# Sheet1.net
KiCad netlist of a schematic drawn in Altium Designer
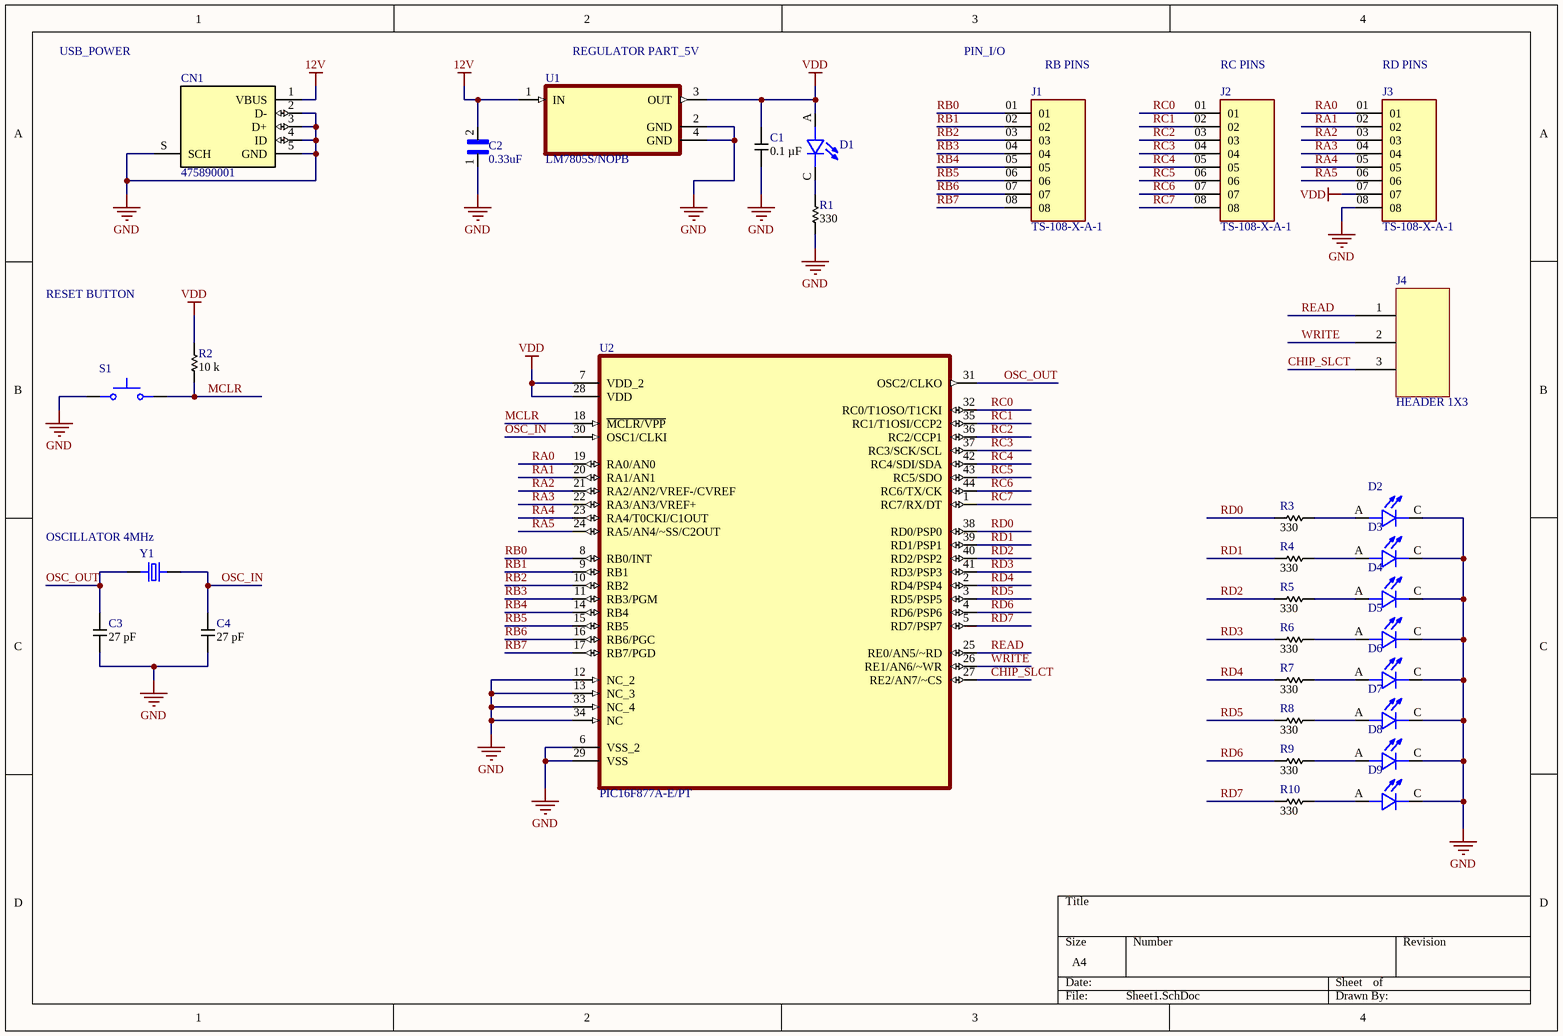
[diagram p0: Sheet1.SchDoc]

(export (version "E")
  (design (tool "Eeschema 10.0.6"))
  (components
    (comp (ref "C1")
      (value "CL10B104KB8NNNC")
      (footprint "SAMSUNG_CAP_0603_090")
      (description "CAP CER 0.1UF 50V X7R 0603")
      (fields (field (name "CAPACITANCE") "0.1 µF"))
      (libsource (lib "Ceramic Capacitors") (part "CL10B104KB8NNNC"))
    )
    (comp (ref "C2")
      (value "0.33uF")
      (footprint "CAPC1608X90N")
      (description "0.33 ÂµF Â±10% 50V Ceramic Capacitor X7R 0603 (1608 Metric)")
      (fields (field (name "MP") "C1608X7R1H334K080AC") (field (name "MF") "TDK"))
      (libsource (lib "C1608X7R1H334K080AC_0.33uF") (part "C1608X7R1H334K080AC"))
    )
    (comp (ref "C3")
      (value "CL21C270JBANNNC")
      (footprint "SAMSUNG_CAP_0805_075")
      (description "CAP CER 27PF 50V C0G/NP0 0805")
      (fields (field (name "CAPACITANCE") "27 pF"))
      (libsource (lib "Ceramic Capacitors") (part "CL21C270JBANNNC"))
    )
    (comp (ref "C4")
      (value "CL21C270JBANNNC")
      (footprint "SAMSUNG_CAP_0805_075")
      (description "CAP CER 27PF 50V C0G/NP0 0805")
      (fields (field (name "CAPACITANCE") "27 pF"))
      (libsource (lib "Ceramic Capacitors") (part "CL21C270JBANNNC"))
    )
    (comp (ref "CN1")
      (value "475890001")
      (footprint "MOLEX_475890001")
      (description "CONN RCPT MICRO USB AB 5P SMD RA")
      (libsource (lib "USB, DVI, HDMI Connectors") (part "475890001"))
    )
    (comp (ref "D1")
      (value "MP-2016-1100-30-80")
      (footprint "LED_MP-2016-1100-30-80")
      (description "LED Midpower Lighting series White, warm 3000K, 80 CRI, 27lm 3V 120mA 110Â°")
      (fields (field (name "MF") "Luminus Devices"))
      (libsource (lib "") (part "MP-2016-1100-30-80_1"))
    )
    (comp (ref "D2")
      (value "MP-2016-1100-30-80")
      (footprint "LED_MP-2016-1100-30-80")
      (description "LED Midpower Lighting series White, warm 3000K, 80 CRI, 27lm 3V 120mA 110Â°")
      (fields (field (name "MF") "Luminus Devices"))
      (libsource (lib "MP-2016-1100-30-80") (part "MP-2016-1100-30-80"))
    )
    (comp (ref "D3")
      (value "MP-2016-1100-30-80")
      (footprint "LED_MP-2016-1100-30-80")
      (description "LED Midpower Lighting series White, warm 3000K, 80 CRI, 27lm 3V 120mA 110Â°")
      (fields (field (name "MF") "Luminus Devices"))
      (libsource (lib "MP-2016-1100-30-80") (part "MP-2016-1100-30-80"))
    )
    (comp (ref "D4")
      (value "MP-2016-1100-30-80")
      (footprint "LED_MP-2016-1100-30-80")
      (description "LED Midpower Lighting series White, warm 3000K, 80 CRI, 27lm 3V 120mA 110Â°")
      (fields (field (name "MF") "Luminus Devices"))
      (libsource (lib "MP-2016-1100-30-80") (part "MP-2016-1100-30-80"))
    )
    (comp (ref "D5")
      (value "MP-2016-1100-30-80")
      (footprint "LED_MP-2016-1100-30-80")
      (description "LED Midpower Lighting series White, warm 3000K, 80 CRI, 27lm 3V 120mA 110Â°")
      (fields (field (name "MF") "Luminus Devices"))
      (libsource (lib "MP-2016-1100-30-80") (part "MP-2016-1100-30-80"))
    )
    (comp (ref "D6")
      (value "MP-2016-1100-30-80")
      (footprint "LED_MP-2016-1100-30-80")
      (description "LED Midpower Lighting series White, warm 3000K, 80 CRI, 27lm 3V 120mA 110Â°")
      (fields (field (name "MF") "Luminus Devices"))
      (libsource (lib "MP-2016-1100-30-80") (part "MP-2016-1100-30-80"))
    )
    (comp (ref "D7")
      (value "MP-2016-1100-30-80")
      (footprint "LED_MP-2016-1100-30-80")
      (description "LED Midpower Lighting series White, warm 3000K, 80 CRI, 27lm 3V 120mA 110Â°")
      (fields (field (name "MF") "Luminus Devices"))
      (libsource (lib "MP-2016-1100-30-80") (part "MP-2016-1100-30-80"))
    )
    (comp (ref "D8")
      (value "MP-2016-1100-30-80")
      (footprint "LED_MP-2016-1100-30-80")
      (description "LED Midpower Lighting series White, warm 3000K, 80 CRI, 27lm 3V 120mA 110Â°")
      (fields (field (name "MF") "Luminus Devices"))
      (libsource (lib "MP-2016-1100-30-80") (part "MP-2016-1100-30-80"))
    )
    (comp (ref "D9")
      (value "MP-2016-1100-30-80")
      (footprint "LED_MP-2016-1100-30-80")
      (description "LED Midpower Lighting series White, warm 3000K, 80 CRI, 27lm 3V 120mA 110Â°")
      (fields (field (name "MF") "Luminus Devices"))
      (libsource (lib "MP-2016-1100-30-80") (part "MP-2016-1100-30-80"))
    )
    (comp (ref "J1")
      (value "TS-108-X-A-1")
      (footprint "SAMTEC_TS-108-X-A-1")
      (description "TS Series .100 Single Row Screw Machine Terminal Strip")
      (fields (field (name "MP") "TS-108-G-A-1") (field (name "MF") "Samtec"))
      (libsource (lib "TS-108-X-A-1") (part "TS-108-X-A-1"))
    )
    (comp (ref "J2")
      (value "TS-108-X-A-1")
      (footprint "SAMTEC_TS-108-X-A-1")
      (description "TS Series .100 Single Row Screw Machine Terminal Strip")
      (fields (field (name "MP") "TS-108-G-A-1") (field (name "MF") "Samtec"))
      (libsource (lib "TS-108-X-A-1") (part "TS-108-X-A-1"))
    )
    (comp (ref "J3")
      (value "TS-108-X-A-1")
      (footprint "SAMTEC_TS-108-X-A-1")
      (description "TS Series .100 Single Row Screw Machine Terminal Strip")
      (fields (field (name "MP") "TS-108-G-A-1") (field (name "MF") "Samtec"))
      (libsource (lib "TS-108-X-A-1") (part "TS-108-X-A-1"))
    )
    (comp (ref "J4")
      (value "HEADER 1X3")
      (footprint "HEADER 1X3_2.54")
      (libsource (lib "Sch1-schlib") (part "HEADER 1X3"))
    )
    (comp (ref "R1")
      (value "0603SAJ0331T5E")
      (footprint "ROYALOHM_RES_0603")
      (description "RES SMD 330R OHM 5% 1/10W 0603")
      (fields (field (name "RESISTANCE") "330"))
      (libsource (lib "Chip Resistor - Surface Mount") (part "0603SAJ0331T5E"))
    )
    (comp (ref "R2")
      (value "0603SAJ0103T5E")
      (footprint "ROYALOHM_RES_0603")
      (description "RES SMD 10K OHM 5% 1/10W 0603")
      (fields (field (name "RESISTANCE") "10 k"))
      (libsource (lib "Chip Resistor - Surface Mount") (part "0603SAJ0103T5E"))
    )
    (comp (ref "R3")
      (value "0603SAJ0331T5E")
      (footprint "ROYALOHM_RES_0603")
      (description "RES SMD 330R OHM 5% 1/10W 0603")
      (fields (field (name "RESISTANCE") "330"))
      (libsource (lib "Chip Resistor - Surface Mount") (part "0603SAJ0331T5E"))
    )
    (comp (ref "R4")
      (value "0603SAJ0331T5E")
      (footprint "ROYALOHM_RES_0603")
      (description "RES SMD 330R OHM 5% 1/10W 0603")
      (fields (field (name "RESISTANCE") "330"))
      (libsource (lib "Chip Resistor - Surface Mount") (part "0603SAJ0331T5E"))
    )
    (comp (ref "R5")
      (value "0603SAJ0331T5E")
      (footprint "ROYALOHM_RES_0603")
      (description "RES SMD 330R OHM 5% 1/10W 0603")
      (fields (field (name "RESISTANCE") "330"))
      (libsource (lib "Chip Resistor - Surface Mount") (part "0603SAJ0331T5E"))
    )
    (comp (ref "R6")
      (value "0603SAJ0331T5E")
      (footprint "ROYALOHM_RES_0603")
      (description "RES SMD 330R OHM 5% 1/10W 0603")
      (fields (field (name "RESISTANCE") "330"))
      (libsource (lib "Chip Resistor - Surface Mount") (part "0603SAJ0331T5E"))
    )
    (comp (ref "R7")
      (value "0603SAJ0331T5E")
      (footprint "ROYALOHM_RES_0603")
      (description "RES SMD 330R OHM 5% 1/10W 0603")
      (fields (field (name "RESISTANCE") "330"))
      (libsource (lib "Chip Resistor - Surface Mount") (part "0603SAJ0331T5E"))
    )
    (comp (ref "R8")
      (value "0603SAJ0331T5E")
      (footprint "ROYALOHM_RES_0603")
      (description "RES SMD 330R OHM 5% 1/10W 0603")
      (fields (field (name "RESISTANCE") "330"))
      (libsource (lib "Chip Resistor - Surface Mount") (part "0603SAJ0331T5E"))
    )
    (comp (ref "R9")
      (value "0603SAJ0331T5E")
      (footprint "ROYALOHM_RES_0603")
      (description "RES SMD 330R OHM 5% 1/10W 0603")
      (fields (field (name "RESISTANCE") "330"))
      (libsource (lib "Chip Resistor - Surface Mount") (part "0603SAJ0331T5E"))
    )
    (comp (ref "R10")
      (value "0603SAJ0331T5E")
      (footprint "ROYALOHM_RES_0603")
      (description "RES SMD 330R OHM 5% 1/10W 0603")
      (fields (field (name "RESISTANCE") "330"))
      (libsource (lib "Chip Resistor - Surface Mount") (part "0603SAJ0331T5E"))
    )
    (comp (ref "S1")
      (value "800AWSP9M2QE")
      (footprint "SW_800AWSP9M2QE")
      (description "Pushbutton Switch SPST-NO Standard Through Hole")
      (fields (field (name "MF") "E-Switch"))
      (libsource (lib "800AWSP9M2QE") (part "800AWSP9M2QE"))
    )
    (comp (ref "U1")
      (value "LM7805S/NOPB")
      (footprint "TO254P1524X483-4N")
      (description "1.5-A, 30-V, linear voltage regulator")
      (fields (field (name "MF") "Texas Instruments"))
      (libsource (lib "LM7805S_NOPB") (part "LM7805S/NOPB"))
    )
    (comp (ref "U2")
      (value "PIC16F877A-E/PT")
      (footprint "QFP80P1200X1200X120-44N")
      (description "PIC PICÂ® 16F Microcontroller IC 8-Bit 20MHz 14KB _8K x 14_ FLASH 44-TQFP _10x10_")
      (fields (field (name "MF") "Microchip"))
      (libsource (lib "SnapEDAsch") (part "PIC16F877A-E/PT"))
    )
    (comp (ref "Y1")
      (value "ECS-40-S-5PX-TR")
      (footprint "XTAL_ECS-40-S-5PX-TR")
      (description "4MHz Â±30ppm Crystal Series 150 Ohms HC-49/US")
      (fields (field (name "MF") "ECS Inc."))
      (libsource (lib "SnapEDAsch") (part "ECS-40-S-5PX-TR"))
    )
  )
  (nets
    (net (code "1") (name "/CHIP_SLCT") (class "Default")
      (node (ref "J4") (pin "3") (pintype "passive"))
      (node (ref "U2") (pin "27") (pinfunction "RE2/AN7/~CS_27") (pintype "bidirectional"))
    )
    (net (code "2") (name "/MCLR") (class "Default")
      (node (ref "R2") (pin "1") (pinfunction "1_1") (pintype "passive"))
      (node (ref "S1") (pin "3") (pinfunction "3_3") (pintype "passive"))
      (node (ref "U2") (pin "18") (pinfunction "~{MCLR/VPP}_18") (pintype "input"))
    )
    (net (code "3") (name "/OSC_IN") (class "Default")
      (node (ref "C4") (pin "2") (pinfunction "2_2") (pintype "passive"))
      (node (ref "U2") (pin "30") (pinfunction "OSC1/CLKI_30") (pintype "input"))
      (node (ref "Y1") (pin "2") (pinfunction "2_2") (pintype "passive"))
    )
    (net (code "4") (name "/OSC_OUT") (class "Default")
      (node (ref "C3") (pin "2") (pinfunction "2_2") (pintype "passive"))
      (node (ref "U2") (pin "31") (pinfunction "OSC2/CLKO_31") (pintype "output"))
      (node (ref "Y1") (pin "1") (pinfunction "1_1") (pintype "passive"))
    )
    (net (code "5") (name "/RA0") (class "Default")
      (node (ref "J3") (pin "01") (pinfunction "01_01") (pintype "passive"))
      (node (ref "U2") (pin "19") (pinfunction "RA0/AN0_19") (pintype "bidirectional"))
    )
    (net (code "6") (name "/RA1") (class "Default")
      (node (ref "J3") (pin "02") (pinfunction "02_02") (pintype "passive"))
      (node (ref "U2") (pin "20") (pinfunction "RA1/AN1_20") (pintype "bidirectional"))
    )
    (net (code "7") (name "/RA2") (class "Default")
      (node (ref "J3") (pin "03") (pinfunction "03_03") (pintype "passive"))
      (node (ref "U2") (pin "21") (pinfunction "RA2/AN2/VREF-/CVREF_21") (pintype "bidirectional"))
    )
    (net (code "8") (name "/RA3") (class "Default")
      (node (ref "J3") (pin "04") (pinfunction "04_04") (pintype "passive"))
      (node (ref "U2") (pin "22") (pinfunction "RA3/AN3/VREF+_22") (pintype "bidirectional"))
    )
    (net (code "9") (name "/RA4") (class "Default")
      (node (ref "J3") (pin "05") (pinfunction "05_05") (pintype "passive"))
      (node (ref "U2") (pin "23") (pinfunction "RA4/T0CKI/C1OUT_23") (pintype "bidirectional"))
    )
    (net (code "10") (name "/RA5") (class "Default")
      (node (ref "J3") (pin "06") (pinfunction "06_06") (pintype "passive"))
      (node (ref "U2") (pin "24") (pinfunction "RA5/AN4/~SS/C2OUT_24") (pintype "bidirectional"))
    )
    (net (code "11") (name "/RB0") (class "Default")
      (node (ref "J1") (pin "01") (pinfunction "01_01") (pintype "passive"))
      (node (ref "U2") (pin "8") (pinfunction "RB0/INT_8") (pintype "bidirectional"))
    )
    (net (code "12") (name "/RB1") (class "Default")
      (node (ref "J1") (pin "02") (pinfunction "02_02") (pintype "passive"))
      (node (ref "U2") (pin "9") (pinfunction "RB1_9") (pintype "bidirectional"))
    )
    (net (code "13") (name "/RB2") (class "Default")
      (node (ref "J1") (pin "03") (pinfunction "03_03") (pintype "passive"))
      (node (ref "U2") (pin "10") (pinfunction "RB2_10") (pintype "bidirectional"))
    )
    (net (code "14") (name "/RB3") (class "Default")
      (node (ref "J1") (pin "04") (pinfunction "04_04") (pintype "passive"))
      (node (ref "U2") (pin "11") (pinfunction "RB3/PGM_11") (pintype "bidirectional"))
    )
    (net (code "15") (name "/RB4") (class "Default")
      (node (ref "J1") (pin "05") (pinfunction "05_05") (pintype "passive"))
      (node (ref "U2") (pin "14") (pinfunction "RB4_14") (pintype "bidirectional"))
    )
    (net (code "16") (name "/RB5") (class "Default")
      (node (ref "J1") (pin "06") (pinfunction "06_06") (pintype "passive"))
      (node (ref "U2") (pin "15") (pinfunction "RB5_15") (pintype "bidirectional"))
    )
    (net (code "17") (name "/RB6") (class "Default")
      (node (ref "J1") (pin "07") (pinfunction "07_07") (pintype "passive"))
      (node (ref "U2") (pin "16") (pinfunction "RB6/PGC_16") (pintype "bidirectional"))
    )
    (net (code "18") (name "/RB7") (class "Default")
      (node (ref "J1") (pin "08") (pinfunction "08_08") (pintype "passive"))
      (node (ref "U2") (pin "17") (pinfunction "RB7/PGD_17") (pintype "bidirectional"))
    )
    (net (code "19") (name "/RC0") (class "Default")
      (node (ref "J2") (pin "01") (pinfunction "01_01") (pintype "passive"))
      (node (ref "U2") (pin "32") (pinfunction "RC0/T1OSO/T1CKI_32") (pintype "bidirectional"))
    )
    (net (code "20") (name "/RC1") (class "Default")
      (node (ref "J2") (pin "02") (pinfunction "02_02") (pintype "passive"))
      (node (ref "U2") (pin "35") (pinfunction "RC1/T1OSI/CCP2_35") (pintype "bidirectional"))
    )
    (net (code "21") (name "/RC2") (class "Default")
      (node (ref "J2") (pin "03") (pinfunction "03_03") (pintype "passive"))
      (node (ref "U2") (pin "36") (pinfunction "RC2/CCP1_36") (pintype "bidirectional"))
    )
    (net (code "22") (name "/RC3") (class "Default")
      (node (ref "J2") (pin "04") (pinfunction "04_04") (pintype "passive"))
      (node (ref "U2") (pin "37") (pinfunction "RC3/SCK/SCL_37") (pintype "bidirectional"))
    )
    (net (code "23") (name "/RC4") (class "Default")
      (node (ref "J2") (pin "05") (pinfunction "05_05") (pintype "passive"))
      (node (ref "U2") (pin "42") (pinfunction "RC4/SDI/SDA_42") (pintype "bidirectional"))
    )
    (net (code "24") (name "/RC5") (class "Default")
      (node (ref "J2") (pin "06") (pinfunction "06_06") (pintype "passive"))
      (node (ref "U2") (pin "43") (pinfunction "RC5/SDO_43") (pintype "bidirectional"))
    )
    (net (code "25") (name "/RC6") (class "Default")
      (node (ref "J2") (pin "07") (pinfunction "07_07") (pintype "passive"))
      (node (ref "U2") (pin "44") (pinfunction "RC6/TX/CK_44") (pintype "bidirectional"))
    )
    (net (code "26") (name "/RC7") (class "Default")
      (node (ref "J2") (pin "08") (pinfunction "08_08") (pintype "passive"))
      (node (ref "U2") (pin "1") (pinfunction "RC7/RX/DT_1") (pintype "bidirectional"))
    )
    (net (code "27") (name "/RD0") (class "Default")
      (node (ref "R3") (pin "1") (pinfunction "1_1") (pintype "passive"))
      (node (ref "U2") (pin "38") (pinfunction "RD0/PSP0_38") (pintype "bidirectional"))
    )
    (net (code "28") (name "/RD1") (class "Default")
      (node (ref "R4") (pin "1") (pinfunction "1_1") (pintype "passive"))
      (node (ref "U2") (pin "39") (pinfunction "RD1/PSP1_39") (pintype "bidirectional"))
    )
    (net (code "29") (name "/RD2") (class "Default")
      (node (ref "R5") (pin "1") (pinfunction "1_1") (pintype "passive"))
      (node (ref "U2") (pin "40") (pinfunction "RD2/PSP2_40") (pintype "bidirectional"))
    )
    (net (code "30") (name "/RD3") (class "Default")
      (node (ref "R6") (pin "1") (pinfunction "1_1") (pintype "passive"))
      (node (ref "U2") (pin "41") (pinfunction "RD3/PSP3_41") (pintype "bidirectional"))
    )
    (net (code "31") (name "/RD4") (class "Default")
      (node (ref "R7") (pin "1") (pinfunction "1_1") (pintype "passive"))
      (node (ref "U2") (pin "2") (pinfunction "RD4/PSP4_2") (pintype "bidirectional"))
    )
    (net (code "32") (name "/RD5") (class "Default")
      (node (ref "R8") (pin "1") (pinfunction "1_1") (pintype "passive"))
      (node (ref "U2") (pin "3") (pinfunction "RD5/PSP5_3") (pintype "bidirectional"))
    )
    (net (code "33") (name "/RD6") (class "Default")
      (node (ref "R9") (pin "1") (pinfunction "1_1") (pintype "passive"))
      (node (ref "U2") (pin "4") (pinfunction "RD6/PSP6_4") (pintype "bidirectional"))
    )
    (net (code "34") (name "/RD7") (class "Default")
      (node (ref "R10") (pin "1") (pinfunction "1_1") (pintype "passive"))
      (node (ref "U2") (pin "5") (pinfunction "RD7/PSP7_5") (pintype "bidirectional"))
    )
    (net (code "35") (name "/READ") (class "Default")
      (node (ref "J4") (pin "1") (pintype "passive"))
      (node (ref "U2") (pin "25") (pinfunction "RE0/AN5/~RD_25") (pintype "bidirectional"))
    )
    (net (code "36") (name "/WRITE") (class "Default")
      (node (ref "J4") (pin "2") (pintype "passive"))
      (node (ref "U2") (pin "26") (pinfunction "RE1/AN6/~WR_26") (pintype "bidirectional"))
    )
    (net (code "37") (name "12V") (class "Default")
      (node (ref "C2") (pin "2") (pinfunction "2_2") (pintype "passive"))
      (node (ref "CN1") (pin "1") (pinfunction "VBUS_1") (pintype "passive"))
      (node (ref "U1") (pin "1") (pinfunction "IN_1") (pintype "input"))
    )
    (net (code "38") (name "GND") (class "Default")
      (node (ref "C1") (pin "1") (pinfunction "1_1") (pintype "passive"))
      (node (ref "C2") (pin "1") (pinfunction "1_1") (pintype "passive"))
      (node (ref "C3") (pin "1") (pinfunction "1_1") (pintype "passive"))
      (node (ref "C4") (pin "1") (pinfunction "1_1") (pintype "passive"))
      (node (ref "CN1") (pin "2") (pinfunction "D-_2") (pintype "bidirectional"))
      (node (ref "CN1") (pin "3") (pinfunction "D+_3") (pintype "bidirectional"))
      (node (ref "CN1") (pin "4") (pinfunction "ID_4") (pintype "bidirectional"))
      (node (ref "CN1") (pin "5") (pinfunction "GND_5") (pintype "passive"))
      (node (ref "CN1") (pin "S") (pinfunction "SCH_S") (pintype "passive"))
      (node (ref "D2") (pin "C") (pinfunction "C_C") (pintype "passive"))
      (node (ref "D3") (pin "C") (pinfunction "C_C") (pintype "passive"))
      (node (ref "D4") (pin "C") (pinfunction "C_C") (pintype "passive"))
      (node (ref "D5") (pin "C") (pinfunction "C_C") (pintype "passive"))
      (node (ref "D6") (pin "C") (pinfunction "C_C") (pintype "passive"))
      (node (ref "D7") (pin "C") (pinfunction "C_C") (pintype "passive"))
      (node (ref "D8") (pin "C") (pinfunction "C_C") (pintype "passive"))
      (node (ref "D9") (pin "C") (pinfunction "C_C") (pintype "passive"))
      (node (ref "J3") (pin "08") (pinfunction "08_08") (pintype "passive"))
      (node (ref "R1") (pin "1") (pinfunction "1_1") (pintype "passive"))
      (node (ref "S1") (pin "1") (pinfunction "1_1") (pintype "passive"))
      (node (ref "U1") (pin "2") (pinfunction "GND_2") (pintype "power_in"))
      (node (ref "U1") (pin "4") (pinfunction "GND_4") (pintype "power_in"))
      (node (ref "U2") (pin "12") (pinfunction "NC_2_12") (pintype "input"))
      (node (ref "U2") (pin "13") (pinfunction "NC_3_13") (pintype "input"))
      (node (ref "U2") (pin "29") (pinfunction "VSS_29") (pintype "power_in"))
      (node (ref "U2") (pin "33") (pinfunction "NC_4_33") (pintype "input"))
      (node (ref "U2") (pin "34") (pinfunction "NC_34") (pintype "input"))
      (node (ref "U2") (pin "6") (pinfunction "VSS_2_6") (pintype "power_in"))
    )
    (net (code "39") (name "Net-(D1-PadC)") (class "Default")
      (node (ref "D1") (pin "C") (pinfunction "C_C") (pintype "passive"))
      (node (ref "R1") (pin "2") (pinfunction "2_2") (pintype "passive"))
    )
    (net (code "40") (name "Net-(D2-PadA)") (class "Default")
      (node (ref "D2") (pin "A") (pinfunction "A_A") (pintype "passive"))
      (node (ref "R3") (pin "2") (pinfunction "2_2") (pintype "passive"))
    )
    (net (code "41") (name "Net-(D3-PadA)") (class "Default")
      (node (ref "D3") (pin "A") (pinfunction "A_A") (pintype "passive"))
      (node (ref "R4") (pin "2") (pinfunction "2_2") (pintype "passive"))
    )
    (net (code "42") (name "Net-(D4-PadA)") (class "Default")
      (node (ref "D4") (pin "A") (pinfunction "A_A") (pintype "passive"))
      (node (ref "R5") (pin "2") (pinfunction "2_2") (pintype "passive"))
    )
    (net (code "43") (name "Net-(D5-PadA)") (class "Default")
      (node (ref "D5") (pin "A") (pinfunction "A_A") (pintype "passive"))
      (node (ref "R6") (pin "2") (pinfunction "2_2") (pintype "passive"))
    )
    (net (code "44") (name "Net-(D6-PadA)") (class "Default")
      (node (ref "D6") (pin "A") (pinfunction "A_A") (pintype "passive"))
      (node (ref "R7") (pin "2") (pinfunction "2_2") (pintype "passive"))
    )
    (net (code "45") (name "Net-(D7-PadA)") (class "Default")
      (node (ref "D7") (pin "A") (pinfunction "A_A") (pintype "passive"))
      (node (ref "R8") (pin "2") (pinfunction "2_2") (pintype "passive"))
    )
    (net (code "46") (name "Net-(D8-PadA)") (class "Default")
      (node (ref "D8") (pin "A") (pinfunction "A_A") (pintype "passive"))
      (node (ref "R9") (pin "2") (pinfunction "2_2") (pintype "passive"))
    )
    (net (code "47") (name "Net-(D9-PadA)") (class "Default")
      (node (ref "D9") (pin "A") (pinfunction "A_A") (pintype "passive"))
      (node (ref "R10") (pin "2") (pinfunction "2_2") (pintype "passive"))
    )
    (net (code "48") (name "VDD") (class "Default")
      (node (ref "C1") (pin "2") (pinfunction "2_2") (pintype "passive"))
      (node (ref "D1") (pin "A") (pinfunction "A_A") (pintype "passive"))
      (node (ref "J3") (pin "07") (pinfunction "07_07") (pintype "passive"))
      (node (ref "R2") (pin "2") (pinfunction "2_2") (pintype "passive"))
      (node (ref "U1") (pin "3") (pinfunction "OUT_3") (pintype "output"))
      (node (ref "U2") (pin "28") (pinfunction "VDD_28") (pintype "power_in"))
      (node (ref "U2") (pin "7") (pinfunction "VDD_2_7") (pintype "power_in"))
    )
  )
)
